# 12_LMS2_Power.net
KiCad netlist of a schematic drawn in Altium Designer
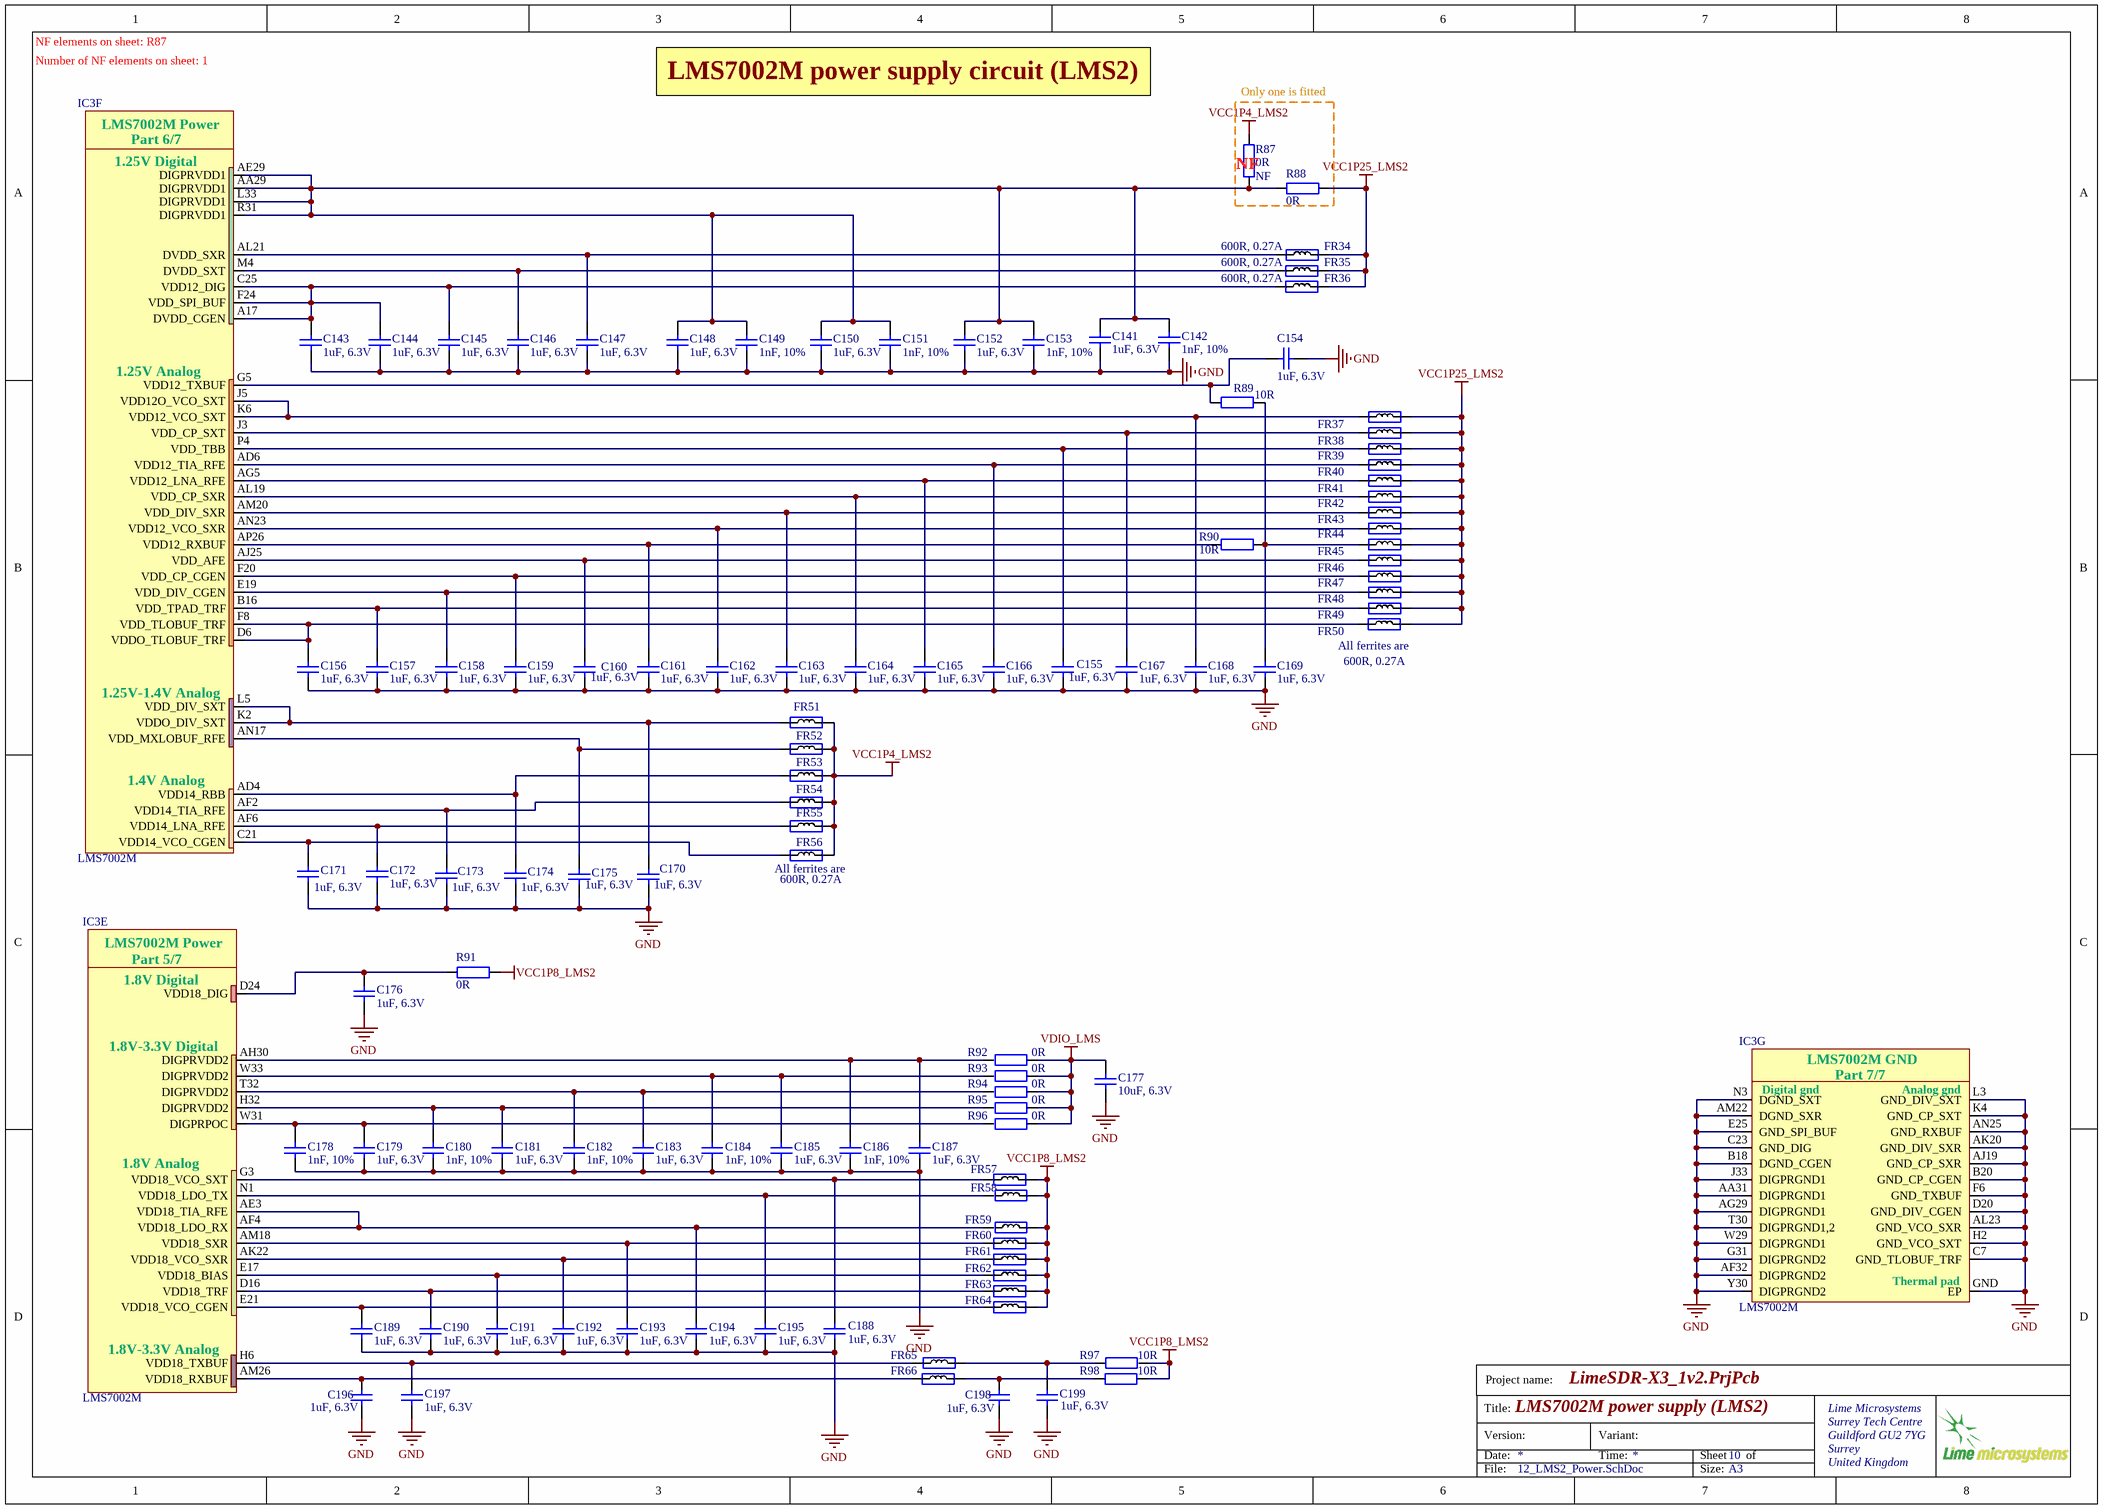
[diagram p0: 12_LMS2_Power.SchDoc]

(export (version "E")
  (design (tool "Eeschema 10.0.6"))
  (components
    (comp (ref "C141")
      (value "1uF, 6.3V")
      (footprint "CAP0201")
      (fields (field (name "TOLERANCE") "±20%") (field (name "MANUFACTURER") "TDK Corporation"))
      (libsource (lib "") (part "Cap_0402_3"))
    )
    (comp (ref "C142")
      (value "1nF, 10%")
      (footprint "CAP0201")
      (fields (field (name "TOLERANCE") "±10%") (field (name "MANUFACTURER") "TDK Corporation"))
      (libsource (lib "") (part "Cap_0402_3"))
    )
    (comp (ref "C143")
      (value "1uF, 6.3V")
      (footprint "CAP0201")
      (fields (field (name "TOLERANCE") "±20%") (field (name "MANUFACTURER") "TDK Corporation"))
      (libsource (lib "LimeMicroAltiumLib_schLib") (part "Cap_0402"))
    )
    (comp (ref "C144")
      (value "1uF, 6.3V")
      (footprint "CAP0201")
      (fields (field (name "TOLERANCE") "±20%") (field (name "MANUFACTURER") "TDK Corporation"))
      (libsource (lib "LimeMicroAltiumLib_schLib") (part "Cap_0402"))
    )
    (comp (ref "C145")
      (value "1uF, 6.3V")
      (footprint "CAP0201")
      (fields (field (name "TOLERANCE") "±20%") (field (name "MANUFACTURER") "TDK Corporation"))
      (libsource (lib "LimeMicroAltiumLib_schLib") (part "Cap_0402"))
    )
    (comp (ref "C146")
      (value "1uF, 6.3V")
      (footprint "CAP0201")
      (fields (field (name "TOLERANCE") "±20%") (field (name "MANUFACTURER") "TDK Corporation"))
      (libsource (lib "") (part "Cap_0402_3"))
    )
    (comp (ref "C147")
      (value "1uF, 6.3V")
      (footprint "CAP0201")
      (fields (field (name "TOLERANCE") "±20%") (field (name "MANUFACTURER") "TDK Corporation"))
      (libsource (lib "LimeMicroAltiumLib_schLib") (part "Cap_0402"))
    )
    (comp (ref "C148")
      (value "1uF, 6.3V")
      (footprint "CAP0201")
      (fields (field (name "TOLERANCE") "±20%") (field (name "MANUFACTURER") "TDK Corporation"))
      (libsource (lib "") (part "Cap_0402_3"))
    )
    (comp (ref "C149")
      (value "1nF, 10%")
      (footprint "CAP0201")
      (fields (field (name "TOLERANCE") "±10%") (field (name "MANUFACTURER") "TDK Corporation"))
      (libsource (lib "") (part "Cap_0402_3"))
    )
    (comp (ref "C150")
      (value "1uF, 6.3V")
      (footprint "CAP0201")
      (fields (field (name "TOLERANCE") "±20%") (field (name "MANUFACTURER") "TDK Corporation"))
      (libsource (lib "") (part "Cap_0402_3"))
    )
    (comp (ref "C151")
      (value "1nF, 10%")
      (footprint "CAP0201")
      (fields (field (name "TOLERANCE") "±10%") (field (name "MANUFACTURER") "TDK Corporation"))
      (libsource (lib "") (part "Cap_0402_3"))
    )
    (comp (ref "C152")
      (value "1uF, 6.3V")
      (footprint "CAP0201")
      (fields (field (name "TOLERANCE") "±20%") (field (name "MANUFACTURER") "TDK Corporation"))
      (libsource (lib "") (part "Cap_0402_3"))
    )
    (comp (ref "C153")
      (value "1nF, 10%")
      (footprint "CAP0201")
      (fields (field (name "TOLERANCE") "±10%") (field (name "MANUFACTURER") "TDK Corporation"))
      (libsource (lib "") (part "Cap_0402_3"))
    )
    (comp (ref "C154")
      (value "1uF, 6.3V")
      (footprint "CAP0201")
      (fields (field (name "TOLERANCE") "±20%") (field (name "MANUFACTURER") "TDK Corporation"))
      (libsource (lib "") (part "Cap_0402_4"))
    )
    (comp (ref "C155")
      (value "1uF, 6.3V")
      (footprint "CAP0201")
      (fields (field (name "TOLERANCE") "±20%") (field (name "MANUFACTURER") "TDK Corporation"))
      (libsource (lib "LimeMicroAltiumLib_schLib") (part "Cap_0402"))
    )
    (comp (ref "C156")
      (value "1uF, 6.3V")
      (footprint "CAP0201")
      (fields (field (name "TOLERANCE") "±20%") (field (name "MANUFACTURER") "TDK Corporation"))
      (libsource (lib "LimeMicroAltiumLib_schLib") (part "Cap_0402"))
    )
    (comp (ref "C157")
      (value "1uF, 6.3V")
      (footprint "CAP0201")
      (fields (field (name "TOLERANCE") "±20%") (field (name "MANUFACTURER") "TDK Corporation"))
      (libsource (lib "LimeMicroAltiumLib_schLib") (part "Cap_0402"))
    )
    (comp (ref "C158")
      (value "1uF, 6.3V")
      (footprint "CAP0201")
      (fields (field (name "TOLERANCE") "±20%") (field (name "MANUFACTURER") "TDK Corporation"))
      (libsource (lib "LimeMicroAltiumLib_schLib") (part "Cap_0402"))
    )
    (comp (ref "C159")
      (value "1uF, 6.3V")
      (footprint "CAP0201")
      (fields (field (name "TOLERANCE") "±20%") (field (name "MANUFACTURER") "TDK Corporation"))
      (libsource (lib "") (part "Cap_0402_3"))
    )
    (comp (ref "C160")
      (value "1uF, 6.3V")
      (footprint "CAP0201")
      (fields (field (name "TOLERANCE") "±20%") (field (name "MANUFACTURER") "TDK Corporation"))
      (libsource (lib "LimeMicroAltiumLib_schLib") (part "Cap_0402"))
    )
    (comp (ref "C161")
      (value "1uF, 6.3V")
      (footprint "CAP0201")
      (fields (field (name "TOLERANCE") "±20%") (field (name "MANUFACTURER") "TDK Corporation"))
      (libsource (lib "LimeMicroAltiumLib_schLib") (part "Cap_0402"))
    )
    (comp (ref "C162")
      (value "1uF, 6.3V")
      (footprint "CAP0201")
      (fields (field (name "TOLERANCE") "±20%") (field (name "MANUFACTURER") "TDK Corporation"))
      (libsource (lib "LimeMicroAltiumLib_schLib") (part "Cap_0402"))
    )
    (comp (ref "C163")
      (value "1uF, 6.3V")
      (footprint "CAP0201")
      (fields (field (name "TOLERANCE") "±20%") (field (name "MANUFACTURER") "TDK Corporation"))
      (libsource (lib "LimeMicroAltiumLib_schLib") (part "Cap_0402"))
    )
    (comp (ref "C164")
      (value "1uF, 6.3V")
      (footprint "CAP0201")
      (fields (field (name "TOLERANCE") "±20%") (field (name "MANUFACTURER") "TDK Corporation"))
      (libsource (lib "LimeMicroAltiumLib_schLib") (part "Cap_0402"))
    )
    (comp (ref "C165")
      (value "1uF, 6.3V")
      (footprint "CAP0201")
      (fields (field (name "TOLERANCE") "±20%") (field (name "MANUFACTURER") "TDK Corporation"))
      (libsource (lib "LimeMicroAltiumLib_schLib") (part "Cap_0402"))
    )
    (comp (ref "C166")
      (value "1uF, 6.3V")
      (footprint "CAP0201")
      (fields (field (name "TOLERANCE") "±20%") (field (name "MANUFACTURER") "TDK Corporation"))
      (libsource (lib "") (part "Cap_0402_3"))
    )
    (comp (ref "C167")
      (value "1uF, 6.3V")
      (footprint "CAP0201")
      (fields (field (name "TOLERANCE") "±20%") (field (name "MANUFACTURER") "TDK Corporation"))
      (libsource (lib "LimeMicroAltiumLib_schLib") (part "Cap_0402"))
    )
    (comp (ref "C168")
      (value "1uF, 6.3V")
      (footprint "CAP0201")
      (fields (field (name "TOLERANCE") "±20%") (field (name "MANUFACTURER") "TDK Corporation"))
      (libsource (lib "") (part "Cap_0402_3"))
    )
    (comp (ref "C169")
      (value "1uF, 6.3V")
      (footprint "CAP0201")
      (fields (field (name "TOLERANCE") "±20%") (field (name "MANUFACTURER") "TDK Corporation"))
      (libsource (lib "") (part "Cap_0402_3"))
    )
    (comp (ref "C170")
      (value "1uF, 6.3V")
      (footprint "CAP0201")
      (fields (field (name "TOLERANCE") "±20%") (field (name "MANUFACTURER") "TDK Corporation"))
      (libsource (lib "LimeMicroAltiumLib_schLib") (part "Cap_0402"))
    )
    (comp (ref "C171")
      (value "1uF, 6.3V")
      (footprint "CAP0201")
      (fields (field (name "TOLERANCE") "±20%") (field (name "MANUFACTURER") "TDK Corporation"))
      (libsource (lib "LimeMicroAltiumLib_schLib") (part "Cap_0402"))
    )
    (comp (ref "C172")
      (value "1uF, 6.3V")
      (footprint "CAP0201")
      (fields (field (name "TOLERANCE") "±20%") (field (name "MANUFACTURER") "TDK Corporation"))
      (libsource (lib "LimeMicroAltiumLib_schLib") (part "Cap_0402"))
    )
    (comp (ref "C173")
      (value "1uF, 6.3V")
      (footprint "CAP0201")
      (fields (field (name "TOLERANCE") "±20%") (field (name "MANUFACTURER") "TDK Corporation"))
      (libsource (lib "") (part "Cap_0402_1"))
    )
    (comp (ref "C174")
      (value "1uF, 6.3V")
      (footprint "CAP0201")
      (fields (field (name "TOLERANCE") "±20%") (field (name "MANUFACTURER") "TDK Corporation"))
      (libsource (lib "") (part "Cap_0402_1"))
    )
    (comp (ref "C175")
      (value "1uF, 6.3V")
      (footprint "CAP0201")
      (fields (field (name "TOLERANCE") "±20%") (field (name "MANUFACTURER") "TDK Corporation"))
      (libsource (lib "LimeMicroAltiumLib_schLib") (part "Cap_0402"))
    )
    (comp (ref "C176")
      (value "1uF, 6.3V")
      (footprint "CAP0201")
      (fields (field (name "TOLERANCE") "±20%") (field (name "MANUFACTURER") "TDK Corporation"))
      (libsource (lib "") (part "Cap_0402_2"))
    )
    (comp (ref "C177")
      (value "10uF, 6.3V")
      (footprint "CAP0603")
      (fields (field (name "TOLERANCE") "±20%") (field (name "MANUFACTURER") "Yageo"))
      (libsource (lib "LimeFPGAboard_schLib") (part "Cap_0603"))
    )
    (comp (ref "C178")
      (value "1nF, 10%")
      (footprint "CAP0201")
      (fields (field (name "TOLERANCE") "±10%") (field (name "MANUFACTURER") "TDK Corporation"))
      (libsource (lib "") (part "Cap_0402_2"))
    )
    (comp (ref "C179")
      (value "1uF, 6.3V")
      (footprint "CAP0201")
      (fields (field (name "TOLERANCE") "±20%") (field (name "MANUFACTURER") "TDK Corporation"))
      (libsource (lib "") (part "Cap_0402_2"))
    )
    (comp (ref "C180")
      (value "1nF, 10%")
      (footprint "CAP0201")
      (fields (field (name "TOLERANCE") "±10%") (field (name "MANUFACTURER") "TDK Corporation"))
      (libsource (lib "") (part "Cap_0402_2"))
    )
    (comp (ref "C181")
      (value "1uF, 6.3V")
      (footprint "CAP0201")
      (fields (field (name "TOLERANCE") "±20%") (field (name "MANUFACTURER") "TDK Corporation"))
      (libsource (lib "") (part "Cap_0402_2"))
    )
    (comp (ref "C182")
      (value "1nF, 10%")
      (footprint "CAP0201")
      (fields (field (name "TOLERANCE") "±10%") (field (name "MANUFACTURER") "TDK Corporation"))
      (libsource (lib "") (part "Cap_0402_2"))
    )
    (comp (ref "C183")
      (value "1uF, 6.3V")
      (footprint "CAP0201")
      (fields (field (name "TOLERANCE") "±20%") (field (name "MANUFACTURER") "TDK Corporation"))
      (libsource (lib "") (part "Cap_0402_2"))
    )
    (comp (ref "C184")
      (value "1nF, 10%")
      (footprint "CAP0201")
      (fields (field (name "TOLERANCE") "±10%") (field (name "MANUFACTURER") "TDK Corporation"))
      (libsource (lib "") (part "Cap_0402_2"))
    )
    (comp (ref "C185")
      (value "1uF, 6.3V")
      (footprint "CAP0201")
      (fields (field (name "TOLERANCE") "±20%") (field (name "MANUFACTURER") "TDK Corporation"))
      (libsource (lib "") (part "Cap_0402_2"))
    )
    (comp (ref "C186")
      (value "1nF, 10%")
      (footprint "CAP0201")
      (fields (field (name "TOLERANCE") "±10%") (field (name "MANUFACTURER") "TDK Corporation"))
      (libsource (lib "") (part "Cap_0402_2"))
    )
    (comp (ref "C187")
      (value "1uF, 6.3V")
      (footprint "CAP0201")
      (fields (field (name "TOLERANCE") "±20%") (field (name "MANUFACTURER") "TDK Corporation"))
      (libsource (lib "") (part "Cap_0402_2"))
    )
    (comp (ref "C188")
      (value "1uF, 6.3V")
      (footprint "CAP0201")
      (fields (field (name "TOLERANCE") "±20%") (field (name "MANUFACTURER") "TDK Corporation"))
      (libsource (lib "") (part "Cap_0402_2"))
    )
    (comp (ref "C189")
      (value "1uF, 6.3V")
      (footprint "CAP0201")
      (fields (field (name "TOLERANCE") "±20%") (field (name "MANUFACTURER") "TDK Corporation"))
      (libsource (lib "") (part "Cap_0402_2"))
    )
    (comp (ref "C190")
      (value "1uF, 6.3V")
      (footprint "CAP0201")
      (fields (field (name "TOLERANCE") "±20%") (field (name "MANUFACTURER") "TDK Corporation"))
      (libsource (lib "") (part "Cap_0402_2"))
    )
    (comp (ref "C191")
      (value "1uF, 6.3V")
      (footprint "CAP0201")
      (fields (field (name "TOLERANCE") "±20%") (field (name "MANUFACTURER") "TDK Corporation"))
      (libsource (lib "") (part "Cap_0402_2"))
    )
    (comp (ref "C192")
      (value "1uF, 6.3V")
      (footprint "CAP0201")
      (fields (field (name "TOLERANCE") "±20%") (field (name "MANUFACTURER") "TDK Corporation"))
      (libsource (lib "") (part "Cap_0402_2"))
    )
    (comp (ref "C193")
      (value "1uF, 6.3V")
      (footprint "CAP0201")
      (fields (field (name "TOLERANCE") "±20%") (field (name "MANUFACTURER") "TDK Corporation"))
      (libsource (lib "") (part "Cap_0402_2"))
    )
    (comp (ref "C194")
      (value "1uF, 6.3V")
      (footprint "CAP0201")
      (fields (field (name "TOLERANCE") "±20%") (field (name "MANUFACTURER") "TDK Corporation"))
      (libsource (lib "") (part "Cap_0402_2"))
    )
    (comp (ref "C195")
      (value "1uF, 6.3V")
      (footprint "CAP0201")
      (fields (field (name "TOLERANCE") "±20%") (field (name "MANUFACTURER") "TDK Corporation"))
      (libsource (lib "") (part "Cap_0402_2"))
    )
    (comp (ref "C196")
      (value "1uF, 6.3V")
      (footprint "CAP0201")
      (fields (field (name "TOLERANCE") "±20%") (field (name "MANUFACTURER") "TDK Corporation"))
      (libsource (lib "") (part "Cap_0402_2"))
    )
    (comp (ref "C197")
      (value "1uF, 6.3V")
      (footprint "CAP0201")
      (fields (field (name "TOLERANCE") "±20%") (field (name "MANUFACTURER") "TDK Corporation"))
      (libsource (lib "") (part "Cap_0402_2"))
    )
    (comp (ref "C198")
      (value "1uF, 6.3V")
      (footprint "CAP0201")
      (fields (field (name "TOLERANCE") "±20%") (field (name "MANUFACTURER") "TDK Corporation"))
      (libsource (lib "") (part "Cap_0402_2"))
    )
    (comp (ref "C199")
      (value "1uF, 6.3V")
      (footprint "CAP0201")
      (fields (field (name "TOLERANCE") "±20%") (field (name "MANUFACTURER") "TDK Corporation"))
      (libsource (lib "") (part "Cap_0402_2"))
    )
    (comp (ref "FR34")
      (value "600R, 0.27A")
      (footprint "RES0201")
      (fields (field (name "MANUFACTURER") "Taiyo Yuden"))
      (libsource (lib "LimeMicroAltiumLib_schLib") (part "Ferrite"))
    )
    (comp (ref "FR35")
      (value "600R, 0.27A")
      (footprint "RES0201")
      (fields (field (name "MANUFACTURER") "Taiyo Yuden"))
      (libsource (lib "") (part "Ferrite_1"))
    )
    (comp (ref "FR36")
      (value "600R, 0.27A")
      (footprint "RES0201")
      (fields (field (name "MANUFACTURER") "Taiyo Yuden"))
      (libsource (lib "") (part "Ferrite_1"))
    )
    (comp (ref "FR37")
      (value "600R, 0.27A")
      (footprint "RES0201")
      (fields (field (name "MANUFACTURER") "Taiyo Yuden"))
      (libsource (lib "LimeMicroAltiumLib_schLib") (part "Ferrite"))
    )
    (comp (ref "FR38")
      (value "600R, 0.27A")
      (footprint "RES0201")
      (fields (field (name "MANUFACTURER") "Taiyo Yuden"))
      (libsource (lib "LimeMicroAltiumLib_schLib") (part "Ferrite"))
    )
    (comp (ref "FR39")
      (value "600R, 0.27A")
      (footprint "RES0201")
      (fields (field (name "MANUFACTURER") "Taiyo Yuden"))
      (libsource (lib "LimeMicroAltiumLib_schLib") (part "Ferrite"))
    )
    (comp (ref "FR40")
      (value "600R, 0.27A")
      (footprint "RES0201")
      (fields (field (name "MANUFACTURER") "Taiyo Yuden"))
      (libsource (lib "LimeMicroAltiumLib_schLib") (part "Ferrite"))
    )
    (comp (ref "FR41")
      (value "600R, 0.27A")
      (footprint "RES0201")
      (fields (field (name "MANUFACTURER") "Taiyo Yuden"))
      (libsource (lib "LimeMicroAltiumLib_schLib") (part "Ferrite"))
    )
    (comp (ref "FR42")
      (value "600R, 0.27A")
      (footprint "RES0201")
      (fields (field (name "MANUFACTURER") "Taiyo Yuden"))
      (libsource (lib "LimeMicroAltiumLib_schLib") (part "Ferrite"))
    )
    (comp (ref "FR43")
      (value "600R, 0.27A")
      (footprint "RES0201")
      (fields (field (name "MANUFACTURER") "Taiyo Yuden"))
      (libsource (lib "LimeMicroAltiumLib_schLib") (part "Ferrite"))
    )
    (comp (ref "FR44")
      (value "600R, 0.27A")
      (footprint "RES0201")
      (fields (field (name "MANUFACTURER") "Taiyo Yuden"))
      (libsource (lib "LimeMicroAltiumLib_schLib") (part "Ferrite"))
    )
    (comp (ref "FR45")
      (value "600R, 0.27A")
      (footprint "RES0201")
      (fields (field (name "MANUFACTURER") "Taiyo Yuden"))
      (libsource (lib "LimeMicroAltiumLib_schLib") (part "Ferrite"))
    )
    (comp (ref "FR46")
      (value "600R, 0.27A")
      (footprint "RES0201")
      (fields (field (name "MANUFACTURER") "Taiyo Yuden"))
      (libsource (lib "LimeMicroAltiumLib_schLib") (part "Ferrite"))
    )
    (comp (ref "FR47")
      (value "600R, 0.27A")
      (footprint "RES0201")
      (fields (field (name "MANUFACTURER") "Taiyo Yuden"))
      (libsource (lib "LimeMicroAltiumLib_schLib") (part "Ferrite"))
    )
    (comp (ref "FR48")
      (value "600R, 0.27A")
      (footprint "RES0201")
      (fields (field (name "MANUFACTURER") "Taiyo Yuden"))
      (libsource (lib "LimeMicroAltiumLib_schLib") (part "Ferrite"))
    )
    (comp (ref "FR49")
      (value "600R, 0.27A")
      (footprint "RES0201")
      (fields (field (name "MANUFACTURER") "Taiyo Yuden"))
      (libsource (lib "LimeMicroAltiumLib_schLib") (part "Ferrite"))
    )
    (comp (ref "FR50")
      (value "600R, 0.27A")
      (footprint "RES0201")
      (fields (field (name "MANUFACTURER") "Taiyo Yuden"))
      (libsource (lib "") (part "Ferrite_1"))
    )
    (comp (ref "FR51")
      (value "600R, 0.27A")
      (footprint "RES0201")
      (fields (field (name "MANUFACTURER") "Taiyo Yuden"))
      (libsource (lib "") (part "Ferrite_1"))
    )
    (comp (ref "FR52")
      (value "600R, 0.27A")
      (footprint "RES0201")
      (fields (field (name "MANUFACTURER") "Taiyo Yuden"))
      (libsource (lib "") (part "Ferrite_1"))
    )
    (comp (ref "FR53")
      (value "600R, 0.27A")
      (footprint "RES0201")
      (fields (field (name "MANUFACTURER") "Taiyo Yuden"))
      (libsource (lib "") (part "Ferrite_1"))
    )
    (comp (ref "FR54")
      (value "600R, 0.27A")
      (footprint "RES0201")
      (fields (field (name "MANUFACTURER") "Taiyo Yuden"))
      (libsource (lib "") (part "Ferrite_1"))
    )
    (comp (ref "FR55")
      (value "600R, 0.27A")
      (footprint "RES0201")
      (fields (field (name "MANUFACTURER") "Taiyo Yuden"))
      (libsource (lib "") (part "Ferrite_1"))
    )
    (comp (ref "FR56")
      (value "600R, 0.27A")
      (footprint "RES0201")
      (fields (field (name "MANUFACTURER") "Taiyo Yuden"))
      (libsource (lib "") (part "Ferrite_1"))
    )
    (comp (ref "FR57")
      (value "600R, 0.27A")
      (footprint "RES0201")
      (fields (field (name "MANUFACTURER") "Taiyo Yuden"))
      (libsource (lib "") (part "Ferrite_1"))
    )
    (comp (ref "FR58")
      (value "600R, 0.27A")
      (footprint "RES0201")
      (fields (field (name "MANUFACTURER") "Taiyo Yuden"))
      (libsource (lib "") (part "Ferrite_2"))
    )
    (comp (ref "FR59")
      (value "600R, 0.27A")
      (footprint "RES0201")
      (fields (field (name "MANUFACTURER") "Taiyo Yuden"))
      (libsource (lib "") (part "Ferrite_2"))
    )
    (comp (ref "FR60")
      (value "600R, 0.27A")
      (footprint "RES0201")
      (fields (field (name "MANUFACTURER") "Taiyo Yuden"))
      (libsource (lib "") (part "Ferrite_1"))
    )
    (comp (ref "FR61")
      (value "600R, 0.27A")
      (footprint "RES0201")
      (fields (field (name "MANUFACTURER") "Taiyo Yuden"))
      (libsource (lib "") (part "Ferrite_1"))
    )
    (comp (ref "FR62")
      (value "600R, 0.27A")
      (footprint "RES0201")
      (fields (field (name "MANUFACTURER") "Taiyo Yuden"))
      (libsource (lib "") (part "Ferrite_1"))
    )
    (comp (ref "FR63")
      (value "600R, 0.27A")
      (footprint "RES0201")
      (fields (field (name "MANUFACTURER") "Taiyo Yuden"))
      (libsource (lib "") (part "Ferrite_1"))
    )
    (comp (ref "FR64")
      (value "600R, 0.27A")
      (footprint "RES0201")
      (fields (field (name "MANUFACTURER") "Taiyo Yuden"))
      (libsource (lib "") (part "Ferrite_1"))
    )
    (comp (ref "FR65")
      (value "600R, 0.27A")
      (footprint "RES0201")
      (fields (field (name "MANUFACTURER") "Taiyo Yuden"))
      (libsource (lib "") (part "Ferrite_2"))
    )
    (comp (ref "FR66")
      (value "600R, 0.27A")
      (footprint "RES0201")
      (fields (field (name "MANUFACTURER") "Taiyo Yuden"))
      (libsource (lib "") (part "Ferrite_1"))
    )
    (comp (ref "IC3")
      (value "LMS7002M")
      (footprint "LMS7002M_v5")
      (description "Schematic symbol revision 4. Default footprint - 0.31mm pad")
      (fields (field (name "MANUFACTURER") "Lime Microsystems"))
      (libsource (lib "LimeMicroAltiumLib_schLib_r04") (part "LMS7002Mr4"))
    )
    (comp (ref "R87")
      (value "0R")
      (footprint "RES0402")
      (fields
        (field (name "ASSEMBLY INFO") "NF")
        (field (name "MANUFACTURER") "Yageo")
        (field (name "TOLERANCE") "Jumper")
      )
      (libsource (lib "LimeMicroAltiumLib_schLib") (part "Res_0402"))
    )
    (comp (ref "R88")
      (value "0R")
      (footprint "RES0402")
      (fields (field (name "MANUFACTURER") "Yageo") (field (name "TOLERANCE") "Jumper"))
      (libsource (lib "") (part "Res_0402_1"))
    )
    (comp (ref "R89")
      (value "10R")
      (footprint "RES0201")
      (fields
        (field (name "MANUFACTURER") "Panasonic Electronic Components")
        (field (name "TOLERANCE") "±1%")
      )
      (libsource (lib "LimeMicroAltiumLib_schLib") (part "Res_0402"))
    )
    (comp (ref "R90")
      (value "10R")
      (footprint "RES0201")
      (fields
        (field (name "MANUFACTURER") "Panasonic Electronic Components")
        (field (name "TOLERANCE") "±1%")
      )
      (libsource (lib "LimeMicroAltiumLib_schLib") (part "Res_0402"))
    )
    (comp (ref "R91")
      (value "0R")
      (footprint "RES0201")
      (fields (field (name "MANUFACTURER") "Rohm Semiconductor") (field (name "TOLERANCE") "Jumper"))
      (libsource (lib "LimeMicroAltiumLib_schLib") (part "Res_0402"))
    )
    (comp (ref "R92")
      (value "0R")
      (footprint "RES0402")
      (fields (field (name "MANUFACTURER") "Yageo") (field (name "TOLERANCE") "Jumper"))
      (libsource (lib "LimeMicroAltiumLib_schLib") (part "Res_0402"))
    )
    (comp (ref "R93")
      (value "0R")
      (footprint "RES0402")
      (fields (field (name "MANUFACTURER") "Yageo") (field (name "TOLERANCE") "Jumper"))
      (libsource (lib "LimeMicroAltiumLib_schLib") (part "Res_0402"))
    )
    (comp (ref "R94")
      (value "0R")
      (footprint "RES0402")
      (fields (field (name "MANUFACTURER") "Yageo") (field (name "TOLERANCE") "Jumper"))
      (libsource (lib "LimeMicroAltiumLib_schLib") (part "Res_0402"))
    )
    (comp (ref "R95")
      (value "0R")
      (footprint "RES0402")
      (fields (field (name "MANUFACTURER") "Yageo") (field (name "TOLERANCE") "Jumper"))
      (libsource (lib "LimeMicroAltiumLib_schLib") (part "Res_0402"))
    )
    (comp (ref "R96")
      (value "0R")
      (footprint "RES0402")
      (fields (field (name "MANUFACTURER") "Yageo") (field (name "TOLERANCE") "Jumper"))
      (libsource (lib "LimeMicroAltiumLib_schLib") (part "Res_0402"))
    )
    (comp (ref "R97")
      (value "10R")
      (footprint "RES0201")
      (fields
        (field (name "MANUFACTURER") "Panasonic Electronic Components")
        (field (name "TOLERANCE") "±1%")
      )
      (libsource (lib "LimeMicroAltiumLib_schLib") (part "Res_0402"))
    )
    (comp (ref "R98")
      (value "10R")
      (footprint "RES0201")
      (fields
        (field (name "MANUFACTURER") "Panasonic Electronic Components")
        (field (name "TOLERANCE") "±1%")
      )
      (libsource (lib "LimeMicroAltiumLib_schLib") (part "Res_0402"))
    )
  )
  (nets
    (net (code "1") (name "GND") (class "Default")
      (node (ref "C141") (pin "2") (pinfunction "2_2") (pintype "passive"))
      (node (ref "C142") (pin "2") (pinfunction "2_2") (pintype "passive"))
      (node (ref "C143") (pin "2") (pinfunction "2_2") (pintype "passive"))
      (node (ref "C144") (pin "2") (pinfunction "2_2") (pintype "passive"))
      (node (ref "C145") (pin "2") (pinfunction "2_2") (pintype "passive"))
      (node (ref "C146") (pin "1") (pinfunction "1_1") (pintype "passive"))
      (node (ref "C147") (pin "2") (pinfunction "2_2") (pintype "passive"))
      (node (ref "C148") (pin "2") (pinfunction "2_2") (pintype "passive"))
      (node (ref "C149") (pin "2") (pinfunction "2_2") (pintype "passive"))
      (node (ref "C150") (pin "2") (pinfunction "2_2") (pintype "passive"))
      (node (ref "C151") (pin "2") (pinfunction "2_2") (pintype "passive"))
      (node (ref "C152") (pin "2") (pinfunction "2_2") (pintype "passive"))
      (node (ref "C153") (pin "2") (pinfunction "2_2") (pintype "passive"))
      (node (ref "C154") (pin "2") (pinfunction "2_2") (pintype "passive"))
      (node (ref "C155") (pin "2") (pinfunction "2_2") (pintype "passive"))
      (node (ref "C156") (pin "2") (pinfunction "2_2") (pintype "passive"))
      (node (ref "C157") (pin "2") (pinfunction "2_2") (pintype "passive"))
      (node (ref "C158") (pin "2") (pinfunction "2_2") (pintype "passive"))
      (node (ref "C159") (pin "1") (pinfunction "1_1") (pintype "passive"))
      (node (ref "C160") (pin "2") (pinfunction "2_2") (pintype "passive"))
      (node (ref "C161") (pin "2") (pinfunction "2_2") (pintype "passive"))
      (node (ref "C162") (pin "2") (pinfunction "2_2") (pintype "passive"))
      (node (ref "C163") (pin "2") (pinfunction "2_2") (pintype "passive"))
      (node (ref "C164") (pin "2") (pinfunction "2_2") (pintype "passive"))
      (node (ref "C165") (pin "2") (pinfunction "2_2") (pintype "passive"))
      (node (ref "C166") (pin "1") (pinfunction "1_1") (pintype "passive"))
      (node (ref "C167") (pin "2") (pinfunction "2_2") (pintype "passive"))
      (node (ref "C168") (pin "1") (pinfunction "1_1") (pintype "passive"))
      (node (ref "C169") (pin "1") (pinfunction "1_1") (pintype "passive"))
      (node (ref "C170") (pin "2") (pinfunction "2_2") (pintype "passive"))
      (node (ref "C171") (pin "2") (pinfunction "2_2") (pintype "passive"))
      (node (ref "C172") (pin "2") (pinfunction "2_2") (pintype "passive"))
      (node (ref "C173") (pin "2") (pinfunction "2_2") (pintype "passive"))
      (node (ref "C174") (pin "2") (pinfunction "2_2") (pintype "passive"))
      (node (ref "C175") (pin "2") (pinfunction "2_2") (pintype "passive"))
      (node (ref "C176") (pin "2") (pinfunction "2_2") (pintype "passive"))
      (node (ref "C177") (pin "1") (pinfunction "1_1") (pintype "passive"))
      (node (ref "C178") (pin "2") (pinfunction "2_2") (pintype "passive"))
      (node (ref "C179") (pin "2") (pinfunction "2_2") (pintype "passive"))
      (node (ref "C180") (pin "2") (pinfunction "2_2") (pintype "passive"))
      (node (ref "C181") (pin "2") (pinfunction "2_2") (pintype "passive"))
      (node (ref "C182") (pin "2") (pinfunction "2_2") (pintype "passive"))
      (node (ref "C183") (pin "2") (pinfunction "2_2") (pintype "passive"))
      (node (ref "C184") (pin "2") (pinfunction "2_2") (pintype "passive"))
      (node (ref "C185") (pin "2") (pinfunction "2_2") (pintype "passive"))
      (node (ref "C186") (pin "2") (pinfunction "2_2") (pintype "passive"))
      (node (ref "C187") (pin "2") (pinfunction "2_2") (pintype "passive"))
      (node (ref "C188") (pin "2") (pinfunction "2_2") (pintype "passive"))
      (node (ref "C189") (pin "2") (pinfunction "2_2") (pintype "passive"))
      (node (ref "C190") (pin "2") (pinfunction "2_2") (pintype "passive"))
      (node (ref "C191") (pin "2") (pinfunction "2_2") (pintype "passive"))
      (node (ref "C192") (pin "2") (pinfunction "2_2") (pintype "passive"))
      (node (ref "C193") (pin "2") (pinfunction "2_2") (pintype "passive"))
      (node (ref "C194") (pin "2") (pinfunction "2_2") (pintype "passive"))
      (node (ref "C195") (pin "2") (pinfunction "2_2") (pintype "passive"))
      (node (ref "C196") (pin "2") (pinfunction "2_2") (pintype "passive"))
      (node (ref "C197") (pin "2") (pinfunction "2_2") (pintype "passive"))
      (node (ref "C198") (pin "2") (pinfunction "2_2") (pintype "passive"))
      (node (ref "C199") (pin "2") (pinfunction "2_2") (pintype "passive"))
      (node (ref "IC3") (pin "AA31") (pinfunction "DIGPRGND1_AA31") (pintype "passive"))
      (node (ref "IC3") (pin "AF32") (pinfunction "DIGPRGND2_AF32") (pintype "passive"))
      (node (ref "IC3") (pin "AG29") (pinfunction "DIGPRGND1_AG29") (pintype "passive"))
      (node (ref "IC3") (pin "AJ19") (pinfunction "GND_CP_SXR_AJ19") (pintype "passive"))
      (node (ref "IC3") (pin "AK20") (pinfunction "GND_DIV_SXR_AK20") (pintype "passive"))
      (node (ref "IC3") (pin "AL23") (pinfunction "GND_VCO_SXR_AL23") (pintype "passive"))
      (node (ref "IC3") (pin "AM22") (pinfunction "DGND_SXR_AM22") (pintype "passive"))
      (node (ref "IC3") (pin "AN25") (pinfunction "GND_RXBUF_AN25") (pintype "passive"))
      (node (ref "IC3") (pin "B18") (pinfunction "DGND_CGEN_B18") (pintype "passive"))
      (node (ref "IC3") (pin "B20") (pinfunction "GND_CP_CGEN_B20") (pintype "passive"))
      (node (ref "IC3") (pin "C23") (pinfunction "GND_DIG_C23") (pintype "passive"))
      (node (ref "IC3") (pin "C7") (pinfunction "GND_TLOBUF_TRF_C7") (pintype "passive"))
      (node (ref "IC3") (pin "D20") (pinfunction "GND_DIV_CGEN_D20") (pintype "passive"))
      (node (ref "IC3") (pin "E25") (pinfunction "GND_SPI_BUF_E25") (pintype "passive"))
      (node (ref "IC3") (pin "F6") (pinfunction "GND_TXBUF_F6") (pintype "passive"))
      (node (ref "IC3") (pin "G31") (pinfunction "DIGPRGND2_G31") (pintype "passive"))
      (node (ref "IC3") (pin "GND") (pinfunction "EP_GND") (pintype "passive"))
      (node (ref "IC3") (pin "H2") (pinfunction "GND_VCO_SXT_H2") (pintype "passive"))
      (node (ref "IC3") (pin "J33") (pinfunction "DIGPRGND1_J33") (pintype "passive"))
      (node (ref "IC3") (pin "K4") (pinfunction "GND_CP_SXT_K4") (pintype "passive"))
      (node (ref "IC3") (pin "L3") (pinfunction "GND_DIV_SXT_L3") (pintype "passive"))
      (node (ref "IC3") (pin "N3") (pinfunction "DGND_SXT_N3") (pintype "passive"))
      (node (ref "IC3") (pin "T30") (pinfunction "DIGPRGND1,2_T30") (pintype "passive"))
      (node (ref "IC3") (pin "W29") (pinfunction "DIGPRGND1_W29") (pintype "passive"))
      (node (ref "IC3") (pin "Y30") (pinfunction "DIGPRGND2_Y30") (pintype "passive"))
    )
    (net (code "2") (name "Net-(C141-Pad1)") (class "Default")
      (node (ref "C141") (pin "1") (pinfunction "1_1") (pintype "passive"))
      (node (ref "C142") (pin "1") (pinfunction "1_1") (pintype "passive"))
      (node (ref "C148") (pin "1") (pinfunction "1_1") (pintype "passive"))
      (node (ref "C149") (pin "1") (pinfunction "1_1") (pintype "passive"))
      (node (ref "C150") (pin "1") (pinfunction "1_1") (pintype "passive"))
      (node (ref "C151") (pin "1") (pinfunction "1_1") (pintype "passive"))
      (node (ref "C152") (pin "1") (pinfunction "1_1") (pintype "passive"))
      (node (ref "C153") (pin "1") (pinfunction "1_1") (pintype "passive"))
      (node (ref "IC3") (pin "AA29") (pinfunction "DIGPRVDD1_AA29") (pintype "power_in"))
      (node (ref "IC3") (pin "AE29") (pinfunction "DIGPRVDD1_AE29") (pintype "power_in"))
      (node (ref "IC3") (pin "L33") (pinfunction "DIGPRVDD1_L33") (pintype "power_in"))
      (node (ref "IC3") (pin "R31") (pinfunction "DIGPRVDD1_R31") (pintype "power_in"))
      (node (ref "R87") (pin "2") (pinfunction "2_2") (pintype "passive"))
      (node (ref "R88") (pin "2") (pinfunction "2_2") (pintype "passive"))
    )
    (net (code "3") (name "Net-(C169-Pad2)") (class "Default")
      (node (ref "C169") (pin "2") (pinfunction "2_2") (pintype "passive"))
      (node (ref "FR45") (pin "1") (pinfunction "1_1") (pintype "passive"))
      (node (ref "R89") (pin "2") (pinfunction "2_2") (pintype "passive"))
      (node (ref "R90") (pin "2") (pinfunction "2_2") (pintype "passive"))
    )
    (net (code "4") (name "Net-(C180-Pad1)") (class "Default")
      (node (ref "C180") (pin "1") (pinfunction "1_1") (pintype "passive"))
      (node (ref "C181") (pin "1") (pinfunction "1_1") (pintype "passive"))
      (node (ref "IC3") (pin "H32") (pinfunction "DIGPRVDD2_H32") (pintype "power_in"))
      (node (ref "R95") (pin "2") (pinfunction "2_2") (pintype "passive"))
    )
    (net (code "5") (name "Net-(C182-Pad1)") (class "Default")
      (node (ref "C182") (pin "1") (pinfunction "1_1") (pintype "passive"))
      (node (ref "C183") (pin "1") (pinfunction "1_1") (pintype "passive"))
      (node (ref "IC3") (pin "T32") (pinfunction "DIGPRVDD2_T32") (pintype "power_in"))
      (node (ref "R94") (pin "2") (pinfunction "2_2") (pintype "passive"))
    )
    (net (code "6") (name "Net-(C184-Pad1)") (class "Default")
      (node (ref "C184") (pin "1") (pinfunction "1_1") (pintype "passive"))
      (node (ref "C185") (pin "1") (pinfunction "1_1") (pintype "passive"))
      (node (ref "IC3") (pin "W33") (pinfunction "DIGPRVDD2_W33") (pintype "power_in"))
      (node (ref "R93") (pin "2") (pinfunction "2_2") (pintype "passive"))
    )
    (net (code "7") (name "Net-(C186-Pad1)") (class "Default")
      (node (ref "C186") (pin "1") (pinfunction "1_1") (pintype "passive"))
      (node (ref "C187") (pin "1") (pinfunction "1_1") (pintype "passive"))
      (node (ref "IC3") (pin "AH30") (pinfunction "DIGPRVDD2_AH30") (pintype "power_in"))
      (node (ref "R92") (pin "2") (pinfunction "2_2") (pintype "passive"))
    )
    (net (code "8") (name "Net-(C198-Pad1)") (class "Default")
      (node (ref "C198") (pin "1") (pinfunction "1_1") (pintype "passive"))
      (node (ref "FR66") (pin "2") (pinfunction "2_2") (pintype "passive"))
      (node (ref "R98") (pin "2") (pinfunction "2_2") (pintype "passive"))
    )
    (net (code "9") (name "Net-(C199-Pad1)") (class "Default")
      (node (ref "C199") (pin "1") (pinfunction "1_1") (pintype "passive"))
      (node (ref "FR65") (pin "1") (pinfunction "1_1") (pintype "passive"))
      (node (ref "R97") (pin "1") (pinfunction "1_1") (pintype "passive"))
    )
    (net (code "10") (name "Net-(IC3E-DIGPRPOC)") (class "Default")
      (node (ref "C178") (pin "1") (pinfunction "1_1") (pintype "passive"))
      (node (ref "C179") (pin "1") (pinfunction "1_1") (pintype "passive"))
      (node (ref "IC3") (pin "W31") (pinfunction "DIGPRPOC_W31") (pintype "power_in"))
      (node (ref "R96") (pin "2") (pinfunction "2_2") (pintype "passive"))
    )
    (net (code "11") (name "Net-(IC3E-VDD18_BIAS)") (class "Default")
      (node (ref "C191") (pin "1") (pinfunction "1_1") (pintype "passive"))
      (node (ref "FR62") (pin "1") (pinfunction "1_1") (pintype "passive"))
      (node (ref "IC3") (pin "E17") (pinfunction "VDD18_BIAS_E17") (pintype "power_in"))
    )
    (net (code "12") (name "Net-(IC3E-VDD18_DIG)") (class "Default")
      (node (ref "C176") (pin "1") (pinfunction "1_1") (pintype "passive"))
      (node (ref "IC3") (pin "D24") (pinfunction "VDD18_DIG_D24") (pintype "power_in"))
      (node (ref "R91") (pin "1") (pinfunction "1_1") (pintype "passive"))
    )
    (net (code "13") (name "Net-(IC3E-VDD18_LDO_RX)") (class "Default")
      (node (ref "C194") (pin "1") (pinfunction "1_1") (pintype "passive"))
      (node (ref "FR59") (pin "2") (pinfunction "2_2") (pintype "passive"))
      (node (ref "IC3") (pin "AE3") (pinfunction "VDD18_TIA_RFE_AE3") (pintype "power_in"))
      (node (ref "IC3") (pin "AF4") (pinfunction "VDD18_LDO_RX_AF4") (pintype "power_in"))
    )
    (net (code "14") (name "Net-(IC3E-VDD18_LDO_TX)") (class "Default")
      (node (ref "C195") (pin "1") (pinfunction "1_1") (pintype "passive"))
      (node (ref "FR58") (pin "2") (pinfunction "2_2") (pintype "passive"))
      (node (ref "IC3") (pin "N1") (pinfunction "VDD18_LDO_TX_N1") (pintype "power_in"))
    )
    (net (code "15") (name "Net-(IC3E-VDD18_RXBUF)") (class "Default")
      (node (ref "C196") (pin "1") (pinfunction "1_1") (pintype "passive"))
      (node (ref "FR66") (pin "1") (pinfunction "1_1") (pintype "passive"))
      (node (ref "IC3") (pin "AM26") (pinfunction "VDD18_RXBUF_AM26") (pintype "power_in"))
    )
    (net (code "16") (name "Net-(IC3E-VDD18_SXR)") (class "Default")
      (node (ref "C193") (pin "1") (pinfunction "1_1") (pintype "passive"))
      (node (ref "FR60") (pin "1") (pinfunction "1_1") (pintype "passive"))
      (node (ref "IC3") (pin "AM18") (pinfunction "VDD18_SXR_AM18") (pintype "power_in"))
    )
    (net (code "17") (name "Net-(IC3E-VDD18_TRF)") (class "Default")
      (node (ref "C190") (pin "1") (pinfunction "1_1") (pintype "passive"))
      (node (ref "FR63") (pin "1") (pinfunction "1_1") (pintype "passive"))
      (node (ref "IC3") (pin "D16") (pinfunction "VDD18_TRF_D16") (pintype "power_in"))
    )
    (net (code "18") (name "Net-(IC3E-VDD18_TXBUF)") (class "Default")
      (node (ref "C197") (pin "1") (pinfunction "1_1") (pintype "passive"))
      (node (ref "FR65") (pin "2") (pinfunction "2_2") (pintype "passive"))
      (node (ref "IC3") (pin "H6") (pinfunction "VDD18_TXBUF_H6") (pintype "power_in"))
    )
    (net (code "19") (name "Net-(IC3E-VDD18_VCO_CGEN)") (class "Default")
      (node (ref "C189") (pin "1") (pinfunction "1_1") (pintype "passive"))
      (node (ref "FR64") (pin "1") (pinfunction "1_1") (pintype "passive"))
      (node (ref "IC3") (pin "E21") (pinfunction "VDD18_VCO_CGEN_E21") (pintype "power_in"))
    )
    (net (code "20") (name "Net-(IC3E-VDD18_VCO_SXR)") (class "Default")
      (node (ref "C192") (pin "1") (pinfunction "1_1") (pintype "passive"))
      (node (ref "FR61") (pin "1") (pinfunction "1_1") (pintype "passive"))
      (node (ref "IC3") (pin "AK22") (pinfunction "VDD18_VCO_SXR_AK22") (pintype "power_in"))
    )
    (net (code "21") (name "Net-(IC3E-VDD18_VCO_SXT)") (class "Default")
      (node (ref "C188") (pin "1") (pinfunction "1_1") (pintype "passive"))
      (node (ref "FR57") (pin "1") (pinfunction "1_1") (pintype "passive"))
      (node (ref "IC3") (pin "G3") (pinfunction "VDD18_VCO_SXT_G3") (pintype "power_in"))
    )
    (net (code "22") (name "Net-(IC3F-DVDD_CGEN)") (class "Default")
      (node (ref "C143") (pin "1") (pinfunction "1_1") (pintype "passive"))
      (node (ref "C144") (pin "1") (pinfunction "1_1") (pintype "passive"))
      (node (ref "C145") (pin "1") (pinfunction "1_1") (pintype "passive"))
      (node (ref "FR36") (pin "1") (pinfunction "1_1") (pintype "passive"))
      (node (ref "IC3") (pin "A17") (pinfunction "DVDD_CGEN_A17") (pintype "power_in"))
      (node (ref "IC3") (pin "C25") (pinfunction "VDD12_DIG_C25") (pintype "power_in"))
      (node (ref "IC3") (pin "F24") (pinfunction "VDD_SPI_BUF_F24") (pintype "power_in"))
    )
    (net (code "23") (name "Net-(IC3F-DVDD_SXR)") (class "Default")
      (node (ref "C147") (pin "1") (pinfunction "1_1") (pintype "passive"))
      (node (ref "FR34") (pin "1") (pinfunction "1_1") (pintype "passive"))
      (node (ref "IC3") (pin "AL21") (pinfunction "DVDD_SXR_AL21") (pintype "power_in"))
    )
    (net (code "24") (name "Net-(IC3F-DVDD_SXT)") (class "Default")
      (node (ref "C146") (pin "2") (pinfunction "2_2") (pintype "passive"))
      (node (ref "FR35") (pin "1") (pinfunction "1_1") (pintype "passive"))
      (node (ref "IC3") (pin "M4") (pinfunction "DVDD_SXT_M4") (pintype "power_in"))
    )
    (net (code "25") (name "Net-(IC3F-VDD12O_VCO_SXT)") (class "Default")
      (node (ref "C168") (pin "2") (pinfunction "2_2") (pintype "passive"))
      (node (ref "FR37") (pin "1") (pinfunction "1_1") (pintype "passive"))
      (node (ref "IC3") (pin "J5") (pinfunction "VDD12O_VCO_SXT_J5") (pintype "power_in"))
      (node (ref "IC3") (pin "K6") (pinfunction "VDD12_VCO_SXT_K6") (pintype "power_in"))
    )
    (net (code "26") (name "Net-(IC3F-VDD12_LNA_RFE)") (class "Default")
      (node (ref "C165") (pin "1") (pinfunction "1_1") (pintype "passive"))
      (node (ref "FR41") (pin "1") (pinfunction "1_1") (pintype "passive"))
      (node (ref "IC3") (pin "AG5") (pinfunction "VDD12_LNA_RFE_AG5") (pintype "power_in"))
    )
    (net (code "27") (name "Net-(IC3F-VDD12_RXBUF)") (class "Default")
      (node (ref "C161") (pin "1") (pinfunction "1_1") (pintype "passive"))
      (node (ref "IC3") (pin "AP26") (pinfunction "VDD12_RXBUF_AP26") (pintype "power_in"))
      (node (ref "R90") (pin "1") (pinfunction "1_1") (pintype "passive"))
    )
    (net (code "28") (name "Net-(IC3F-VDD12_TIA_RFE)") (class "Default")
      (node (ref "C166") (pin "2") (pinfunction "2_2") (pintype "passive"))
      (node (ref "FR40") (pin "1") (pinfunction "1_1") (pintype "passive"))
      (node (ref "IC3") (pin "AD6") (pinfunction "VDD12_TIA_RFE_AD6") (pintype "power_in"))
    )
    (net (code "29") (name "Net-(IC3F-VDD12_TXBUF)") (class "Default")
      (node (ref "C154") (pin "1") (pinfunction "1_1") (pintype "passive"))
      (node (ref "IC3") (pin "G5") (pinfunction "VDD12_TXBUF_G5") (pintype "power_in"))
      (node (ref "R89") (pin "1") (pinfunction "1_1") (pintype "passive"))
    )
    (net (code "30") (name "Net-(IC3F-VDD12_VCO_SXR)") (class "Default")
      (node (ref "C162") (pin "1") (pinfunction "1_1") (pintype "passive"))
      (node (ref "FR44") (pin "1") (pinfunction "1_1") (pintype "passive"))
      (node (ref "IC3") (pin "AN23") (pinfunction "VDD12_VCO_SXR_AN23") (pintype "power_in"))
    )
    (net (code "31") (name "Net-(IC3F-VDD14_LNA_RFE)") (class "Default")
      (node (ref "C172") (pin "1") (pinfunction "1_1") (pintype "passive"))
      (node (ref "FR55") (pin "1") (pinfunction "1_1") (pintype "passive"))
      (node (ref "IC3") (pin "AF6") (pinfunction "VDD14_LNA_RFE_AF6") (pintype "power_in"))
    )
    (net (code "32") (name "Net-(IC3F-VDD14_RBB)") (class "Default")
      (node (ref "C174") (pin "1") (pinfunction "1_1") (pintype "passive"))
      (node (ref "FR53") (pin "1") (pinfunction "1_1") (pintype "passive"))
      (node (ref "IC3") (pin "AD4") (pinfunction "VDD14_RBB_AD4") (pintype "power_in"))
    )
    (net (code "33") (name "Net-(IC3F-VDD14_TIA_RFE)") (class "Default")
      (node (ref "C173") (pin "1") (pinfunction "1_1") (pintype "passive"))
      (node (ref "FR54") (pin "1") (pinfunction "1_1") (pintype "passive"))
      (node (ref "IC3") (pin "AF2") (pinfunction "VDD14_TIA_RFE_AF2") (pintype "power_in"))
    )
    (net (code "34") (name "Net-(IC3F-VDD14_VCO_CGEN)") (class "Default")
      (node (ref "C171") (pin "1") (pinfunction "1_1") (pintype "passive"))
      (node (ref "FR56") (pin "1") (pinfunction "1_1") (pintype "passive"))
      (node (ref "IC3") (pin "C21") (pinfunction "VDD14_VCO_CGEN_C21") (pintype "power_in"))
    )
    (net (code "35") (name "Net-(IC3F-VDDO_DIV_SXT)") (class "Default")
      (node (ref "C170") (pin "1") (pinfunction "1_1") (pintype "passive"))
      (node (ref "FR51") (pin "1") (pinfunction "1_1") (pintype "passive"))
      (node (ref "IC3") (pin "K2") (pinfunction "VDDO_DIV_SXT_K2") (pintype "power_in"))
      (node (ref "IC3") (pin "L5") (pinfunction "VDD_DIV_SXT_L5") (pintype "power_in"))
    )
    (net (code "36") (name "Net-(IC3F-VDDO_TLOBUF_TRF)") (class "Default")
      (node (ref "C156") (pin "1") (pinfunction "1_1") (pintype "passive"))
      (node (ref "FR50") (pin "1") (pinfunction "1_1") (pintype "passive"))
      (node (ref "IC3") (pin "D6") (pinfunction "VDDO_TLOBUF_TRF_D6") (pintype "power_in"))
      (node (ref "IC3") (pin "F8") (pinfunction "VDD_TLOBUF_TRF_F8") (pintype "power_in"))
    )
    (net (code "37") (name "Net-(IC3F-VDD_AFE)") (class "Default")
      (node (ref "C160") (pin "1") (pinfunction "1_1") (pintype "passive"))
      (node (ref "FR46") (pin "1") (pinfunction "1_1") (pintype "passive"))
      (node (ref "IC3") (pin "AJ25") (pinfunction "VDD_AFE_AJ25") (pintype "power_in"))
    )
    (net (code "38") (name "Net-(IC3F-VDD_CP_CGEN)") (class "Default")
      (node (ref "C159") (pin "2") (pinfunction "2_2") (pintype "passive"))
      (node (ref "FR47") (pin "1") (pinfunction "1_1") (pintype "passive"))
      (node (ref "IC3") (pin "F20") (pinfunction "VDD_CP_CGEN_F20") (pintype "power_in"))
    )
    (net (code "39") (name "Net-(IC3F-VDD_CP_SXR)") (class "Default")
      (node (ref "C164") (pin "1") (pinfunction "1_1") (pintype "passive"))
      (node (ref "FR42") (pin "1") (pinfunction "1_1") (pintype "passive"))
      (node (ref "IC3") (pin "AL19") (pinfunction "VDD_CP_SXR_AL19") (pintype "power_in"))
    )
    (net (code "40") (name "Net-(IC3F-VDD_CP_SXT)") (class "Default")
      (node (ref "C167") (pin "1") (pinfunction "1_1") (pintype "passive"))
      (node (ref "FR38") (pin "1") (pinfunction "1_1") (pintype "passive"))
      (node (ref "IC3") (pin "J3") (pinfunction "VDD_CP_SXT_J3") (pintype "power_in"))
    )
    (net (code "41") (name "Net-(IC3F-VDD_DIV_CGEN)") (class "Default")
      (node (ref "C158") (pin "1") (pinfunction "1_1") (pintype "passive"))
      (node (ref "FR48") (pin "1") (pinfunction "1_1") (pintype "passive"))
      (node (ref "IC3") (pin "E19") (pinfunction "VDD_DIV_CGEN_E19") (pintype "power_in"))
    )
    (net (code "42") (name "Net-(IC3F-VDD_DIV_SXR)") (class "Default")
      (node (ref "C163") (pin "1") (pinfunction "1_1") (pintype "passive"))
      (node (ref "FR43") (pin "1") (pinfunction "1_1") (pintype "passive"))
      (node (ref "IC3") (pin "AM20") (pinfunction "VDD_DIV_SXR_AM20") (pintype "power_in"))
    )
    (net (code "43") (name "Net-(IC3F-VDD_MXLOBUF_RFE)") (class "Default")
      (node (ref "C175") (pin "1") (pinfunction "1_1") (pintype "passive"))
      (node (ref "FR52") (pin "1") (pinfunction "1_1") (pintype "passive"))
      (node (ref "IC3") (pin "AN17") (pinfunction "VDD_MXLOBUF_RFE_AN17") (pintype "power_in"))
    )
    (net (code "44") (name "Net-(IC3F-VDD_TBB)") (class "Default")
      (node (ref "C155") (pin "1") (pinfunction "1_1") (pintype "passive"))
      (node (ref "FR39") (pin "1") (pinfunction "1_1") (pintype "passive"))
      (node (ref "IC3") (pin "P4") (pinfunction "VDD_TBB_P4") (pintype "power_in"))
    )
    (net (code "45") (name "Net-(IC3F-VDD_TPAD_TRF)") (class "Default")
      (node (ref "C157") (pin "1") (pinfunction "1_1") (pintype "passive"))
      (node (ref "FR49") (pin "1") (pinfunction "1_1") (pintype "passive"))
      (node (ref "IC3") (pin "B16") (pinfunction "VDD_TPAD_TRF_B16") (pintype "power_in"))
    )
    (net (code "46") (name "VCC1P4_LMS2") (class "Default")
      (node (ref "FR51") (pin "2") (pinfunction "2_2") (pintype "passive"))
      (node (ref "FR52") (pin "2") (pinfunction "2_2") (pintype "passive"))
      (node (ref "FR53") (pin "2") (pinfunction "2_2") (pintype "passive"))
      (node (ref "FR54") (pin "2") (pinfunction "2_2") (pintype "passive"))
      (node (ref "FR55") (pin "2") (pinfunction "2_2") (pintype "passive"))
      (node (ref "FR56") (pin "2") (pinfunction "2_2") (pintype "passive"))
      (node (ref "R87") (pin "1") (pinfunction "1_1") (pintype "passive"))
    )
    (net (code "47") (name "VCC1P8_LMS2") (class "Default")
      (node (ref "FR57") (pin "2") (pinfunction "2_2") (pintype "passive"))
      (node (ref "FR58") (pin "1") (pinfunction "1_1") (pintype "passive"))
      (node (ref "FR59") (pin "1") (pinfunction "1_1") (pintype "passive"))
      (node (ref "FR60") (pin "2") (pinfunction "2_2") (pintype "passive"))
      (node (ref "FR61") (pin "2") (pinfunction "2_2") (pintype "passive"))
      (node (ref "FR62") (pin "2") (pinfunction "2_2") (pintype "passive"))
      (node (ref "FR63") (pin "2") (pinfunction "2_2") (pintype "passive"))
      (node (ref "FR64") (pin "2") (pinfunction "2_2") (pintype "passive"))
      (node (ref "R91") (pin "2") (pinfunction "2_2") (pintype "passive"))
      (node (ref "R97") (pin "2") (pinfunction "2_2") (pintype "passive"))
      (node (ref "R98") (pin "1") (pinfunction "1_1") (pintype "passive"))
    )
    (net (code "48") (name "VCC1P25_LMS2") (class "Default")
      (node (ref "FR34") (pin "2") (pinfunction "2_2") (pintype "passive"))
      (node (ref "FR35") (pin "2") (pinfunction "2_2") (pintype "passive"))
      (node (ref "FR36") (pin "2") (pinfunction "2_2") (pintype "passive"))
      (node (ref "FR37") (pin "2") (pinfunction "2_2") (pintype "passive"))
      (node (ref "FR38") (pin "2") (pinfunction "2_2") (pintype "passive"))
      (node (ref "FR39") (pin "2") (pinfunction "2_2") (pintype "passive"))
      (node (ref "FR40") (pin "2") (pinfunction "2_2") (pintype "passive"))
      (node (ref "FR41") (pin "2") (pinfunction "2_2") (pintype "passive"))
      (node (ref "FR42") (pin "2") (pinfunction "2_2") (pintype "passive"))
      (node (ref "FR43") (pin "2") (pinfunction "2_2") (pintype "passive"))
      (node (ref "FR44") (pin "2") (pinfunction "2_2") (pintype "passive"))
      (node (ref "FR45") (pin "2") (pinfunction "2_2") (pintype "passive"))
      (node (ref "FR46") (pin "2") (pinfunction "2_2") (pintype "passive"))
      (node (ref "FR47") (pin "2") (pinfunction "2_2") (pintype "passive"))
      (node (ref "FR48") (pin "2") (pinfunction "2_2") (pintype "passive"))
      (node (ref "FR49") (pin "2") (pinfunction "2_2") (pintype "passive"))
      (node (ref "FR50") (pin "2") (pinfunction "2_2") (pintype "passive"))
      (node (ref "R88") (pin "1") (pinfunction "1_1") (pintype "passive"))
    )
    (net (code "49") (name "VDIO_LMS") (class "Default")
      (node (ref "C177") (pin "2") (pinfunction "2_2") (pintype "passive"))
      (node (ref "R92") (pin "1") (pinfunction "1_1") (pintype "passive"))
      (node (ref "R93") (pin "1") (pinfunction "1_1") (pintype "passive"))
      (node (ref "R94") (pin "1") (pinfunction "1_1") (pintype "passive"))
      (node (ref "R95") (pin "1") (pinfunction "1_1") (pintype "passive"))
      (node (ref "R96") (pin "1") (pinfunction "1_1") (pintype "passive"))
    )
  )
)
